# ring24.net
KiCad netlist of a schematic drawn in EAGLE
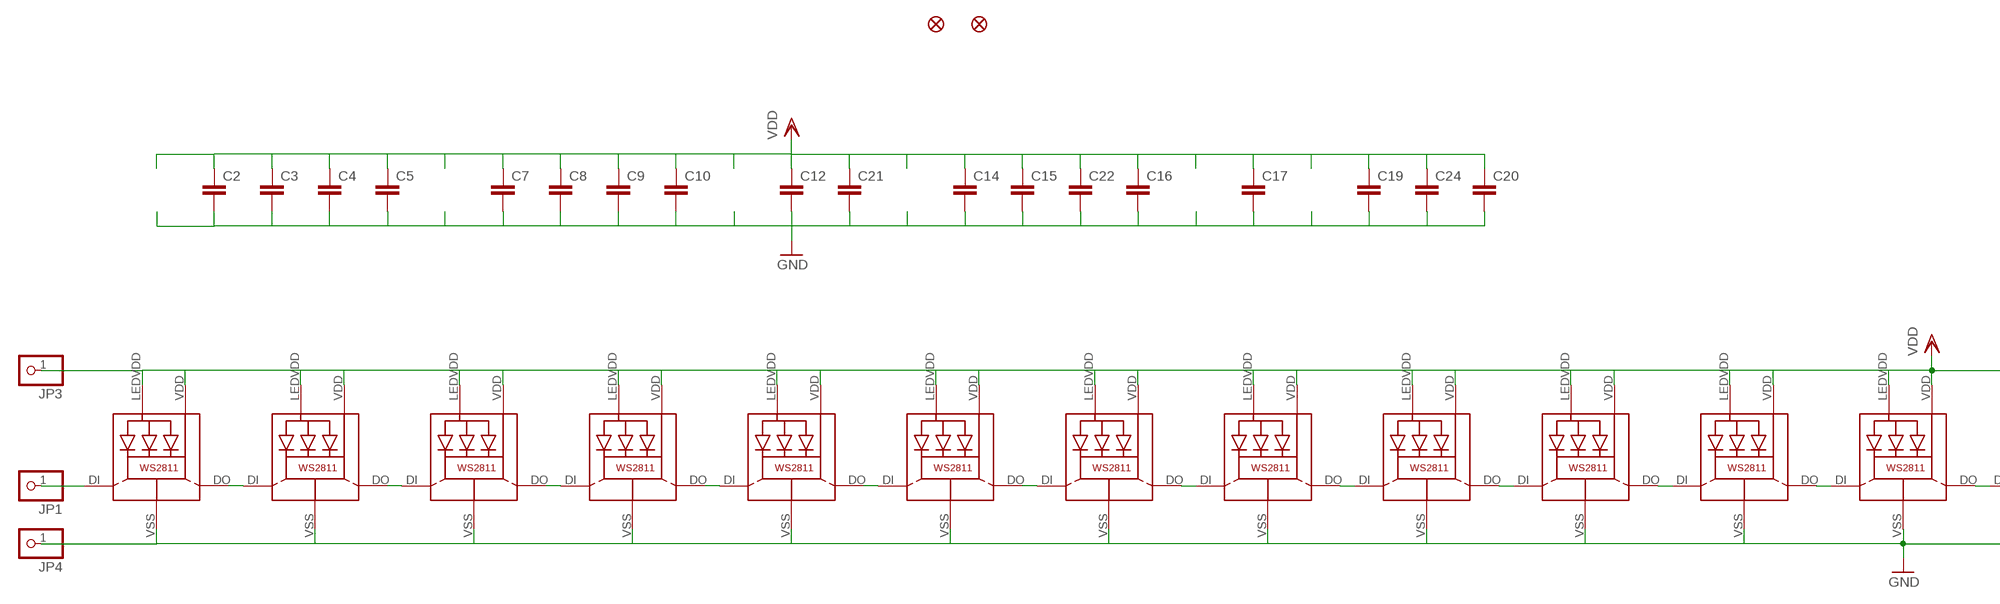
[diagram p0: schematic, sheet 1, part 1 of 2]
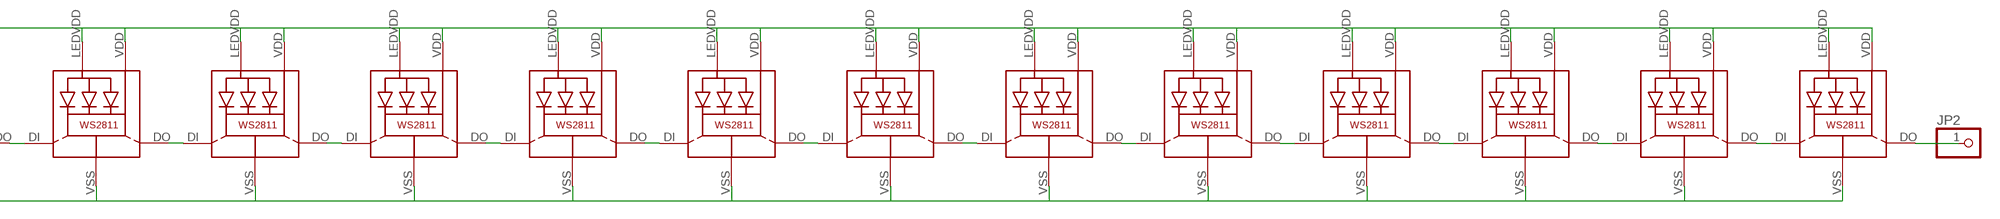
[diagram p1: schematic, sheet 1, part 2 of 2]

(export (version "E")
  (design (tool "Eeschema 10.0.6"))
  (components
    (comp (ref "C2")
      (value "C-EUC0603")
      (footprint "eagle-import:C0603")
      (libsource (lib "eagle-import") (part "C-EUC0603"))
    )
    (comp (ref "C3")
      (value "C-EUC0603")
      (footprint "eagle-import:C0603")
      (libsource (lib "eagle-import") (part "C-EUC0603"))
    )
    (comp (ref "C4")
      (value "C-EUC0603")
      (footprint "eagle-import:C0603")
      (libsource (lib "eagle-import") (part "C-EUC0603"))
    )
    (comp (ref "C5")
      (value "C-EUC0603")
      (footprint "eagle-import:C0603")
      (libsource (lib "eagle-import") (part "C-EUC0603"))
    )
    (comp (ref "C7")
      (value "C-EUC0603")
      (footprint "eagle-import:C0603")
      (libsource (lib "eagle-import") (part "C-EUC0603"))
    )
    (comp (ref "C8")
      (value "C-EUC0603")
      (footprint "eagle-import:C0603")
      (libsource (lib "eagle-import") (part "C-EUC0603"))
    )
    (comp (ref "C9")
      (value "C-EUC0603")
      (footprint "eagle-import:C0603")
      (libsource (lib "eagle-import") (part "C-EUC0603"))
    )
    (comp (ref "C10")
      (value "C-EUC0603")
      (footprint "eagle-import:C0603")
      (libsource (lib "eagle-import") (part "C-EUC0603"))
    )
    (comp (ref "C12")
      (value "C-EUC0603")
      (footprint "eagle-import:C0603")
      (libsource (lib "eagle-import") (part "C-EUC0603"))
    )
    (comp (ref "C14")
      (value "C-EUC0603")
      (footprint "eagle-import:C0603")
      (libsource (lib "eagle-import") (part "C-EUC0603"))
    )
    (comp (ref "C15")
      (value "C-EUC0603")
      (footprint "eagle-import:C0603")
      (libsource (lib "eagle-import") (part "C-EUC0603"))
    )
    (comp (ref "C16")
      (value "C-EUC0603")
      (footprint "eagle-import:C0603")
      (libsource (lib "eagle-import") (part "C-EUC0603"))
    )
    (comp (ref "C17")
      (value "C-EUC0603")
      (footprint "eagle-import:C0603")
      (libsource (lib "eagle-import") (part "C-EUC0603"))
    )
    (comp (ref "C19")
      (value "C-EUC0603")
      (footprint "eagle-import:C0603")
      (libsource (lib "eagle-import") (part "C-EUC0603"))
    )
    (comp (ref "C20")
      (value "C-EUC0603")
      (footprint "eagle-import:C0603")
      (libsource (lib "eagle-import") (part "C-EUC0603"))
    )
    (comp (ref "C21")
      (value "C-EUC0603")
      (footprint "eagle-import:C0603")
      (libsource (lib "eagle-import") (part "C-EUC0603"))
    )
    (comp (ref "C22")
      (value "C-EUC0603")
      (footprint "eagle-import:C0603")
      (libsource (lib "eagle-import") (part "C-EUC0603"))
    )
    (comp (ref "C24")
      (value "C-EUC0603")
      (footprint "eagle-import:C0603")
      (libsource (lib "eagle-import") (part "C-EUC0603"))
    )
    (comp (ref "FID1")
      (value "FIDUCIAL\"\"")
      (footprint "eagle-import:FIDUCIAL_1MM")
      (libsource (lib "eagle-import") (part "FIDUCIAL{dblquote}{dblquote}"))
    )
    (comp (ref "FID2")
      (value "FIDUCIAL\"\"")
      (footprint "eagle-import:FIDUCIAL_1MM")
      (libsource (lib "eagle-import") (part "FIDUCIAL{dblquote}{dblquote}"))
    )
    (comp (ref "JP1")
      (value "PINHD-1X1CB")
      (footprint "eagle-import:1X01-CLEANBIG")
      (libsource (lib "eagle-import") (part "PINHD-1X1CB"))
    )
    (comp (ref "JP2")
      (value "PINHD-1X1CB")
      (footprint "eagle-import:1X01-CLEANBIG")
      (libsource (lib "eagle-import") (part "PINHD-1X1CB"))
    )
    (comp (ref "JP3")
      (value "PINHD-1X1CB")
      (footprint "eagle-import:1X01-CLEANBIG")
      (libsource (lib "eagle-import") (part "PINHD-1X1CB"))
    )
    (comp (ref "JP4")
      (value "PINHD-1X1CB")
      (footprint "eagle-import:1X01-CLEANBIG")
      (libsource (lib "eagle-import") (part "PINHD-1X1CB"))
    )
    (comp (ref "LED1")
      (value "WS28115050")
      (footprint "eagle-import:WS28115050")
      (libsource (lib "eagle-import") (part "WS28115050"))
    )
    (comp (ref "LED2")
      (value "WS28115050")
      (footprint "eagle-import:WS28115050")
      (libsource (lib "eagle-import") (part "WS28115050"))
    )
    (comp (ref "LED3")
      (value "WS28115050")
      (footprint "eagle-import:WS28115050")
      (libsource (lib "eagle-import") (part "WS28115050"))
    )
    (comp (ref "LED4")
      (value "WS28115050")
      (footprint "eagle-import:WS28115050")
      (libsource (lib "eagle-import") (part "WS28115050"))
    )
    (comp (ref "LED5")
      (value "WS28115050")
      (footprint "eagle-import:WS28115050")
      (libsource (lib "eagle-import") (part "WS28115050"))
    )
    (comp (ref "LED6")
      (value "WS28115050")
      (footprint "eagle-import:WS28115050")
      (libsource (lib "eagle-import") (part "WS28115050"))
    )
    (comp (ref "LED7")
      (value "WS28115050")
      (footprint "eagle-import:WS28115050")
      (libsource (lib "eagle-import") (part "WS28115050"))
    )
    (comp (ref "LED8")
      (value "WS28115050")
      (footprint "eagle-import:WS28115050")
      (libsource (lib "eagle-import") (part "WS28115050"))
    )
    (comp (ref "LED9")
      (value "WS28115050")
      (footprint "eagle-import:WS28115050")
      (libsource (lib "eagle-import") (part "WS28115050"))
    )
    (comp (ref "LED10")
      (value "WS28115050")
      (footprint "eagle-import:WS28115050")
      (libsource (lib "eagle-import") (part "WS28115050"))
    )
    (comp (ref "LED11")
      (value "WS28115050")
      (footprint "eagle-import:WS28115050")
      (libsource (lib "eagle-import") (part "WS28115050"))
    )
    (comp (ref "LED12")
      (value "WS28115050")
      (footprint "eagle-import:WS28115050")
      (libsource (lib "eagle-import") (part "WS28115050"))
    )
    (comp (ref "LED13")
      (value "WS28115050")
      (footprint "eagle-import:WS28115050")
      (libsource (lib "eagle-import") (part "WS28115050"))
    )
    (comp (ref "LED14")
      (value "WS28115050")
      (footprint "eagle-import:WS28115050")
      (libsource (lib "eagle-import") (part "WS28115050"))
    )
    (comp (ref "LED15")
      (value "WS28115050")
      (footprint "eagle-import:WS28115050")
      (libsource (lib "eagle-import") (part "WS28115050"))
    )
    (comp (ref "LED16")
      (value "WS28115050")
      (footprint "eagle-import:WS28115050")
      (libsource (lib "eagle-import") (part "WS28115050"))
    )
    (comp (ref "LED17")
      (value "WS28115050")
      (footprint "eagle-import:WS28115050")
      (libsource (lib "eagle-import") (part "WS28115050"))
    )
    (comp (ref "LED18")
      (value "WS28115050")
      (footprint "eagle-import:WS28115050")
      (libsource (lib "eagle-import") (part "WS28115050"))
    )
    (comp (ref "LED19")
      (value "WS28115050")
      (footprint "eagle-import:WS28115050")
      (libsource (lib "eagle-import") (part "WS28115050"))
    )
    (comp (ref "LED20")
      (value "WS28115050")
      (footprint "eagle-import:WS28115050")
      (libsource (lib "eagle-import") (part "WS28115050"))
    )
    (comp (ref "LED21")
      (value "WS28115050")
      (footprint "eagle-import:WS28115050")
      (libsource (lib "eagle-import") (part "WS28115050"))
    )
    (comp (ref "LED22")
      (value "WS28115050")
      (footprint "eagle-import:WS28115050")
      (libsource (lib "eagle-import") (part "WS28115050"))
    )
    (comp (ref "LED23")
      (value "WS28115050")
      (footprint "eagle-import:WS28115050")
      (libsource (lib "eagle-import") (part "WS28115050"))
    )
    (comp (ref "LED24")
      (value "WS28115050")
      (footprint "eagle-import:WS28115050")
      (libsource (lib "eagle-import") (part "WS28115050"))
    )
  )
  (nets
    (net (code "1") (name "GND") (class "Default")
      (node (ref "C10") (pin "2") (pinfunction "2_2") (pintype "passive"))
      (node (ref "C12") (pin "2") (pinfunction "2_2") (pintype "passive"))
      (node (ref "C14") (pin "2") (pinfunction "2_2") (pintype "passive"))
      (node (ref "C15") (pin "2") (pinfunction "2_2") (pintype "passive"))
      (node (ref "C16") (pin "2") (pinfunction "2_2") (pintype "passive"))
      (node (ref "C17") (pin "2") (pinfunction "2_2") (pintype "passive"))
      (node (ref "C19") (pin "2") (pinfunction "2_2") (pintype "passive"))
      (node (ref "C2") (pin "2") (pinfunction "2_2") (pintype "passive"))
      (node (ref "C20") (pin "2") (pinfunction "2_2") (pintype "passive"))
      (node (ref "C21") (pin "2") (pinfunction "2_2") (pintype "passive"))
      (node (ref "C22") (pin "2") (pinfunction "2_2") (pintype "passive"))
      (node (ref "C24") (pin "2") (pinfunction "2_2") (pintype "passive"))
      (node (ref "C3") (pin "2") (pinfunction "2_2") (pintype "passive"))
      (node (ref "C4") (pin "2") (pinfunction "2_2") (pintype "passive"))
      (node (ref "C5") (pin "2") (pinfunction "2_2") (pintype "passive"))
      (node (ref "C7") (pin "2") (pinfunction "2_2") (pintype "passive"))
      (node (ref "C8") (pin "2") (pinfunction "2_2") (pintype "passive"))
      (node (ref "C9") (pin "2") (pinfunction "2_2") (pintype "passive"))
      (node (ref "JP4") (pin "1") (pinfunction "1_1") (pintype "passive"))
      (node (ref "LED1") (pin "VSS") (pinfunction "GND_VSS") (pintype "power_in"))
      (node (ref "LED10") (pin "VSS") (pinfunction "GND_VSS") (pintype "power_in"))
      (node (ref "LED11") (pin "VSS") (pinfunction "GND_VSS") (pintype "power_in"))
      (node (ref "LED12") (pin "VSS") (pinfunction "GND_VSS") (pintype "power_in"))
      (node (ref "LED13") (pin "VSS") (pinfunction "GND_VSS") (pintype "power_in"))
      (node (ref "LED14") (pin "VSS") (pinfunction "GND_VSS") (pintype "power_in"))
      (node (ref "LED15") (pin "VSS") (pinfunction "GND_VSS") (pintype "power_in"))
      (node (ref "LED16") (pin "VSS") (pinfunction "GND_VSS") (pintype "power_in"))
      (node (ref "LED17") (pin "VSS") (pinfunction "GND_VSS") (pintype "power_in"))
      (node (ref "LED18") (pin "VSS") (pinfunction "GND_VSS") (pintype "power_in"))
      (node (ref "LED19") (pin "VSS") (pinfunction "GND_VSS") (pintype "power_in"))
      (node (ref "LED2") (pin "VSS") (pinfunction "GND_VSS") (pintype "power_in"))
      (node (ref "LED20") (pin "VSS") (pinfunction "GND_VSS") (pintype "power_in"))
      (node (ref "LED21") (pin "VSS") (pinfunction "GND_VSS") (pintype "power_in"))
      (node (ref "LED22") (pin "VSS") (pinfunction "GND_VSS") (pintype "power_in"))
      (node (ref "LED23") (pin "VSS") (pinfunction "GND_VSS") (pintype "power_in"))
      (node (ref "LED24") (pin "VSS") (pinfunction "GND_VSS") (pintype "power_in"))
      (node (ref "LED3") (pin "VSS") (pinfunction "GND_VSS") (pintype "power_in"))
      (node (ref "LED4") (pin "VSS") (pinfunction "GND_VSS") (pintype "power_in"))
      (node (ref "LED5") (pin "VSS") (pinfunction "GND_VSS") (pintype "power_in"))
      (node (ref "LED6") (pin "VSS") (pinfunction "GND_VSS") (pintype "power_in"))
      (node (ref "LED7") (pin "VSS") (pinfunction "GND_VSS") (pintype "power_in"))
      (node (ref "LED8") (pin "VSS") (pinfunction "GND_VSS") (pintype "power_in"))
      (node (ref "LED9") (pin "VSS") (pinfunction "GND_VSS") (pintype "power_in"))
    )
    (net (code "2") (name "Net-(JP1-Pad1)") (class "Default")
      (node (ref "JP1") (pin "1") (pinfunction "1_1") (pintype "passive"))
      (node (ref "LED1") (pin "DI") (pinfunction "DI_DI") (pintype "input"))
    )
    (net (code "3") (name "Net-(JP2-Pad1)") (class "Default")
      (node (ref "JP2") (pin "1") (pinfunction "1_1") (pintype "passive"))
      (node (ref "LED24") (pin "DO") (pinfunction "DO_DO") (pintype "output"))
    )
    (net (code "4") (name "Net-(LED1-PadDO)") (class "Default")
      (node (ref "LED1") (pin "DO") (pinfunction "DO_DO") (pintype "output"))
      (node (ref "LED2") (pin "DI") (pinfunction "DI_DI") (pintype "input"))
    )
    (net (code "5") (name "Net-(LED2-PadDO)") (class "Default")
      (node (ref "LED2") (pin "DO") (pinfunction "DO_DO") (pintype "output"))
      (node (ref "LED3") (pin "DI") (pinfunction "DI_DI") (pintype "input"))
    )
    (net (code "6") (name "Net-(LED3-PadDO)") (class "Default")
      (node (ref "LED3") (pin "DO") (pinfunction "DO_DO") (pintype "output"))
      (node (ref "LED4") (pin "DI") (pinfunction "DI_DI") (pintype "input"))
    )
    (net (code "7") (name "Net-(LED4-PadDO)") (class "Default")
      (node (ref "LED4") (pin "DO") (pinfunction "DO_DO") (pintype "output"))
      (node (ref "LED5") (pin "DI") (pinfunction "DI_DI") (pintype "input"))
    )
    (net (code "8") (name "Net-(LED5-PadDO)") (class "Default")
      (node (ref "LED5") (pin "DO") (pinfunction "DO_DO") (pintype "output"))
      (node (ref "LED6") (pin "DI") (pinfunction "DI_DI") (pintype "input"))
    )
    (net (code "9") (name "Net-(LED6-PadDO)") (class "Default")
      (node (ref "LED6") (pin "DO") (pinfunction "DO_DO") (pintype "output"))
      (node (ref "LED7") (pin "DI") (pinfunction "DI_DI") (pintype "input"))
    )
    (net (code "10") (name "Net-(LED7-PadDO)") (class "Default")
      (node (ref "LED7") (pin "DO") (pinfunction "DO_DO") (pintype "output"))
      (node (ref "LED8") (pin "DI") (pinfunction "DI_DI") (pintype "input"))
    )
    (net (code "11") (name "Net-(LED8-PadDO)") (class "Default")
      (node (ref "LED8") (pin "DO") (pinfunction "DO_DO") (pintype "output"))
      (node (ref "LED9") (pin "DI") (pinfunction "DI_DI") (pintype "input"))
    )
    (net (code "12") (name "Net-(LED10-PadDI)") (class "Default")
      (node (ref "LED10") (pin "DI") (pinfunction "DI_DI") (pintype "input"))
      (node (ref "LED9") (pin "DO") (pinfunction "DO_DO") (pintype "output"))
    )
    (net (code "13") (name "Net-(LED10-PadDO)") (class "Default")
      (node (ref "LED10") (pin "DO") (pinfunction "DO_DO") (pintype "output"))
      (node (ref "LED11") (pin "DI") (pinfunction "DI_DI") (pintype "input"))
    )
    (net (code "14") (name "Net-(LED11-PadDO)") (class "Default")
      (node (ref "LED11") (pin "DO") (pinfunction "DO_DO") (pintype "output"))
      (node (ref "LED12") (pin "DI") (pinfunction "DI_DI") (pintype "input"))
    )
    (net (code "15") (name "Net-(LED12-PadDO)") (class "Default")
      (node (ref "LED12") (pin "DO") (pinfunction "DO_DO") (pintype "output"))
      (node (ref "LED13") (pin "DI") (pinfunction "DI_DI") (pintype "input"))
    )
    (net (code "16") (name "Net-(LED13-PadDO)") (class "Default")
      (node (ref "LED13") (pin "DO") (pinfunction "DO_DO") (pintype "output"))
      (node (ref "LED14") (pin "DI") (pinfunction "DI_DI") (pintype "input"))
    )
    (net (code "17") (name "Net-(LED14-PadDO)") (class "Default")
      (node (ref "LED14") (pin "DO") (pinfunction "DO_DO") (pintype "output"))
      (node (ref "LED15") (pin "DI") (pinfunction "DI_DI") (pintype "input"))
    )
    (net (code "18") (name "Net-(LED15-PadDO)") (class "Default")
      (node (ref "LED15") (pin "DO") (pinfunction "DO_DO") (pintype "output"))
      (node (ref "LED16") (pin "DI") (pinfunction "DI_DI") (pintype "input"))
    )
    (net (code "19") (name "Net-(LED16-PadDO)") (class "Default")
      (node (ref "LED16") (pin "DO") (pinfunction "DO_DO") (pintype "output"))
      (node (ref "LED17") (pin "DI") (pinfunction "DI_DI") (pintype "input"))
    )
    (net (code "20") (name "Net-(LED17-PadDO)") (class "Default")
      (node (ref "LED17") (pin "DO") (pinfunction "DO_DO") (pintype "output"))
      (node (ref "LED18") (pin "DI") (pinfunction "DI_DI") (pintype "input"))
    )
    (net (code "21") (name "Net-(LED18-PadDO)") (class "Default")
      (node (ref "LED18") (pin "DO") (pinfunction "DO_DO") (pintype "output"))
      (node (ref "LED19") (pin "DI") (pinfunction "DI_DI") (pintype "input"))
    )
    (net (code "22") (name "Net-(LED19-PadDO)") (class "Default")
      (node (ref "LED19") (pin "DO") (pinfunction "DO_DO") (pintype "output"))
      (node (ref "LED20") (pin "DI") (pinfunction "DI_DI") (pintype "input"))
    )
    (net (code "23") (name "Net-(LED20-PadDO)") (class "Default")
      (node (ref "LED20") (pin "DO") (pinfunction "DO_DO") (pintype "output"))
      (node (ref "LED21") (pin "DI") (pinfunction "DI_DI") (pintype "input"))
    )
    (net (code "24") (name "Net-(LED21-PadDO)") (class "Default")
      (node (ref "LED21") (pin "DO") (pinfunction "DO_DO") (pintype "output"))
      (node (ref "LED22") (pin "DI") (pinfunction "DI_DI") (pintype "input"))
    )
    (net (code "25") (name "Net-(LED22-PadDO)") (class "Default")
      (node (ref "LED22") (pin "DO") (pinfunction "DO_DO") (pintype "output"))
      (node (ref "LED23") (pin "DI") (pinfunction "DI_DI") (pintype "input"))
    )
    (net (code "26") (name "Net-(LED23-PadDO)") (class "Default")
      (node (ref "LED23") (pin "DO") (pinfunction "DO_DO") (pintype "output"))
      (node (ref "LED24") (pin "DI") (pinfunction "DI_DI") (pintype "input"))
    )
    (net (code "27") (name "VDD") (class "Default")
      (node (ref "C10") (pin "1") (pinfunction "1_1") (pintype "passive"))
      (node (ref "C12") (pin "1") (pinfunction "1_1") (pintype "passive"))
      (node (ref "C14") (pin "1") (pinfunction "1_1") (pintype "passive"))
      (node (ref "C15") (pin "1") (pinfunction "1_1") (pintype "passive"))
      (node (ref "C16") (pin "1") (pinfunction "1_1") (pintype "passive"))
      (node (ref "C17") (pin "1") (pinfunction "1_1") (pintype "passive"))
      (node (ref "C19") (pin "1") (pinfunction "1_1") (pintype "passive"))
      (node (ref "C2") (pin "1") (pinfunction "1_1") (pintype "passive"))
      (node (ref "C20") (pin "1") (pinfunction "1_1") (pintype "passive"))
      (node (ref "C21") (pin "1") (pinfunction "1_1") (pintype "passive"))
      (node (ref "C22") (pin "1") (pinfunction "1_1") (pintype "passive"))
      (node (ref "C24") (pin "1") (pinfunction "1_1") (pintype "passive"))
      (node (ref "C3") (pin "1") (pinfunction "1_1") (pintype "passive"))
      (node (ref "C4") (pin "1") (pinfunction "1_1") (pintype "passive"))
      (node (ref "C5") (pin "1") (pinfunction "1_1") (pintype "passive"))
      (node (ref "C7") (pin "1") (pinfunction "1_1") (pintype "passive"))
      (node (ref "C8") (pin "1") (pinfunction "1_1") (pintype "passive"))
      (node (ref "C9") (pin "1") (pinfunction "1_1") (pintype "passive"))
      (node (ref "JP3") (pin "1") (pinfunction "1_1") (pintype "passive"))
      (node (ref "LED1") (pin "LEDVDD") (pinfunction "LEDVDD_LEDVDD") (pintype "power_in"))
      (node (ref "LED1") (pin "VDD") (pinfunction "VDD_VDD") (pintype "power_in"))
      (node (ref "LED10") (pin "LEDVDD") (pinfunction "LEDVDD_LEDVDD") (pintype "power_in"))
      (node (ref "LED10") (pin "VDD") (pinfunction "VDD_VDD") (pintype "power_in"))
      (node (ref "LED11") (pin "LEDVDD") (pinfunction "LEDVDD_LEDVDD") (pintype "power_in"))
      (node (ref "LED11") (pin "VDD") (pinfunction "VDD_VDD") (pintype "power_in"))
      (node (ref "LED12") (pin "LEDVDD") (pinfunction "LEDVDD_LEDVDD") (pintype "power_in"))
      (node (ref "LED12") (pin "VDD") (pinfunction "VDD_VDD") (pintype "power_in"))
      (node (ref "LED13") (pin "LEDVDD") (pinfunction "LEDVDD_LEDVDD") (pintype "power_in"))
      (node (ref "LED13") (pin "VDD") (pinfunction "VDD_VDD") (pintype "power_in"))
      (node (ref "LED14") (pin "LEDVDD") (pinfunction "LEDVDD_LEDVDD") (pintype "power_in"))
      (node (ref "LED14") (pin "VDD") (pinfunction "VDD_VDD") (pintype "power_in"))
      (node (ref "LED15") (pin "LEDVDD") (pinfunction "LEDVDD_LEDVDD") (pintype "power_in"))
      (node (ref "LED15") (pin "VDD") (pinfunction "VDD_VDD") (pintype "power_in"))
      (node (ref "LED16") (pin "LEDVDD") (pinfunction "LEDVDD_LEDVDD") (pintype "power_in"))
      (node (ref "LED16") (pin "VDD") (pinfunction "VDD_VDD") (pintype "power_in"))
      (node (ref "LED17") (pin "LEDVDD") (pinfunction "LEDVDD_LEDVDD") (pintype "power_in"))
      (node (ref "LED17") (pin "VDD") (pinfunction "VDD_VDD") (pintype "power_in"))
      (node (ref "LED18") (pin "LEDVDD") (pinfunction "LEDVDD_LEDVDD") (pintype "power_in"))
      (node (ref "LED18") (pin "VDD") (pinfunction "VDD_VDD") (pintype "power_in"))
      (node (ref "LED19") (pin "LEDVDD") (pinfunction "LEDVDD_LEDVDD") (pintype "power_in"))
      (node (ref "LED19") (pin "VDD") (pinfunction "VDD_VDD") (pintype "power_in"))
      (node (ref "LED2") (pin "LEDVDD") (pinfunction "LEDVDD_LEDVDD") (pintype "power_in"))
      (node (ref "LED2") (pin "VDD") (pinfunction "VDD_VDD") (pintype "power_in"))
      (node (ref "LED20") (pin "LEDVDD") (pinfunction "LEDVDD_LEDVDD") (pintype "power_in"))
      (node (ref "LED20") (pin "VDD") (pinfunction "VDD_VDD") (pintype "power_in"))
      (node (ref "LED21") (pin "LEDVDD") (pinfunction "LEDVDD_LEDVDD") (pintype "power_in"))
      (node (ref "LED21") (pin "VDD") (pinfunction "VDD_VDD") (pintype "power_in"))
      (node (ref "LED22") (pin "LEDVDD") (pinfunction "LEDVDD_LEDVDD") (pintype "power_in"))
      (node (ref "LED22") (pin "VDD") (pinfunction "VDD_VDD") (pintype "power_in"))
      (node (ref "LED23") (pin "LEDVDD") (pinfunction "LEDVDD_LEDVDD") (pintype "power_in"))
      (node (ref "LED23") (pin "VDD") (pinfunction "VDD_VDD") (pintype "power_in"))
      (node (ref "LED24") (pin "LEDVDD") (pinfunction "LEDVDD_LEDVDD") (pintype "power_in"))
      (node (ref "LED24") (pin "VDD") (pinfunction "VDD_VDD") (pintype "power_in"))
      (node (ref "LED3") (pin "LEDVDD") (pinfunction "LEDVDD_LEDVDD") (pintype "power_in"))
      (node (ref "LED3") (pin "VDD") (pinfunction "VDD_VDD") (pintype "power_in"))
      (node (ref "LED4") (pin "LEDVDD") (pinfunction "LEDVDD_LEDVDD") (pintype "power_in"))
      (node (ref "LED4") (pin "VDD") (pinfunction "VDD_VDD") (pintype "power_in"))
      (node (ref "LED5") (pin "LEDVDD") (pinfunction "LEDVDD_LEDVDD") (pintype "power_in"))
      (node (ref "LED5") (pin "VDD") (pinfunction "VDD_VDD") (pintype "power_in"))
      (node (ref "LED6") (pin "LEDVDD") (pinfunction "LEDVDD_LEDVDD") (pintype "power_in"))
      (node (ref "LED6") (pin "VDD") (pinfunction "VDD_VDD") (pintype "power_in"))
      (node (ref "LED7") (pin "LEDVDD") (pinfunction "LEDVDD_LEDVDD") (pintype "power_in"))
      (node (ref "LED7") (pin "VDD") (pinfunction "VDD_VDD") (pintype "power_in"))
      (node (ref "LED8") (pin "LEDVDD") (pinfunction "LEDVDD_LEDVDD") (pintype "power_in"))
      (node (ref "LED8") (pin "VDD") (pinfunction "VDD_VDD") (pintype "power_in"))
      (node (ref "LED9") (pin "LEDVDD") (pinfunction "LEDVDD_LEDVDD") (pintype "power_in"))
      (node (ref "LED9") (pin "VDD") (pinfunction "VDD_VDD") (pintype "power_in"))
    )
  )
)
